# 01_-_CML3_CONNECTOR.net
KiCad netlist of a schematic drawn in Altium Designer
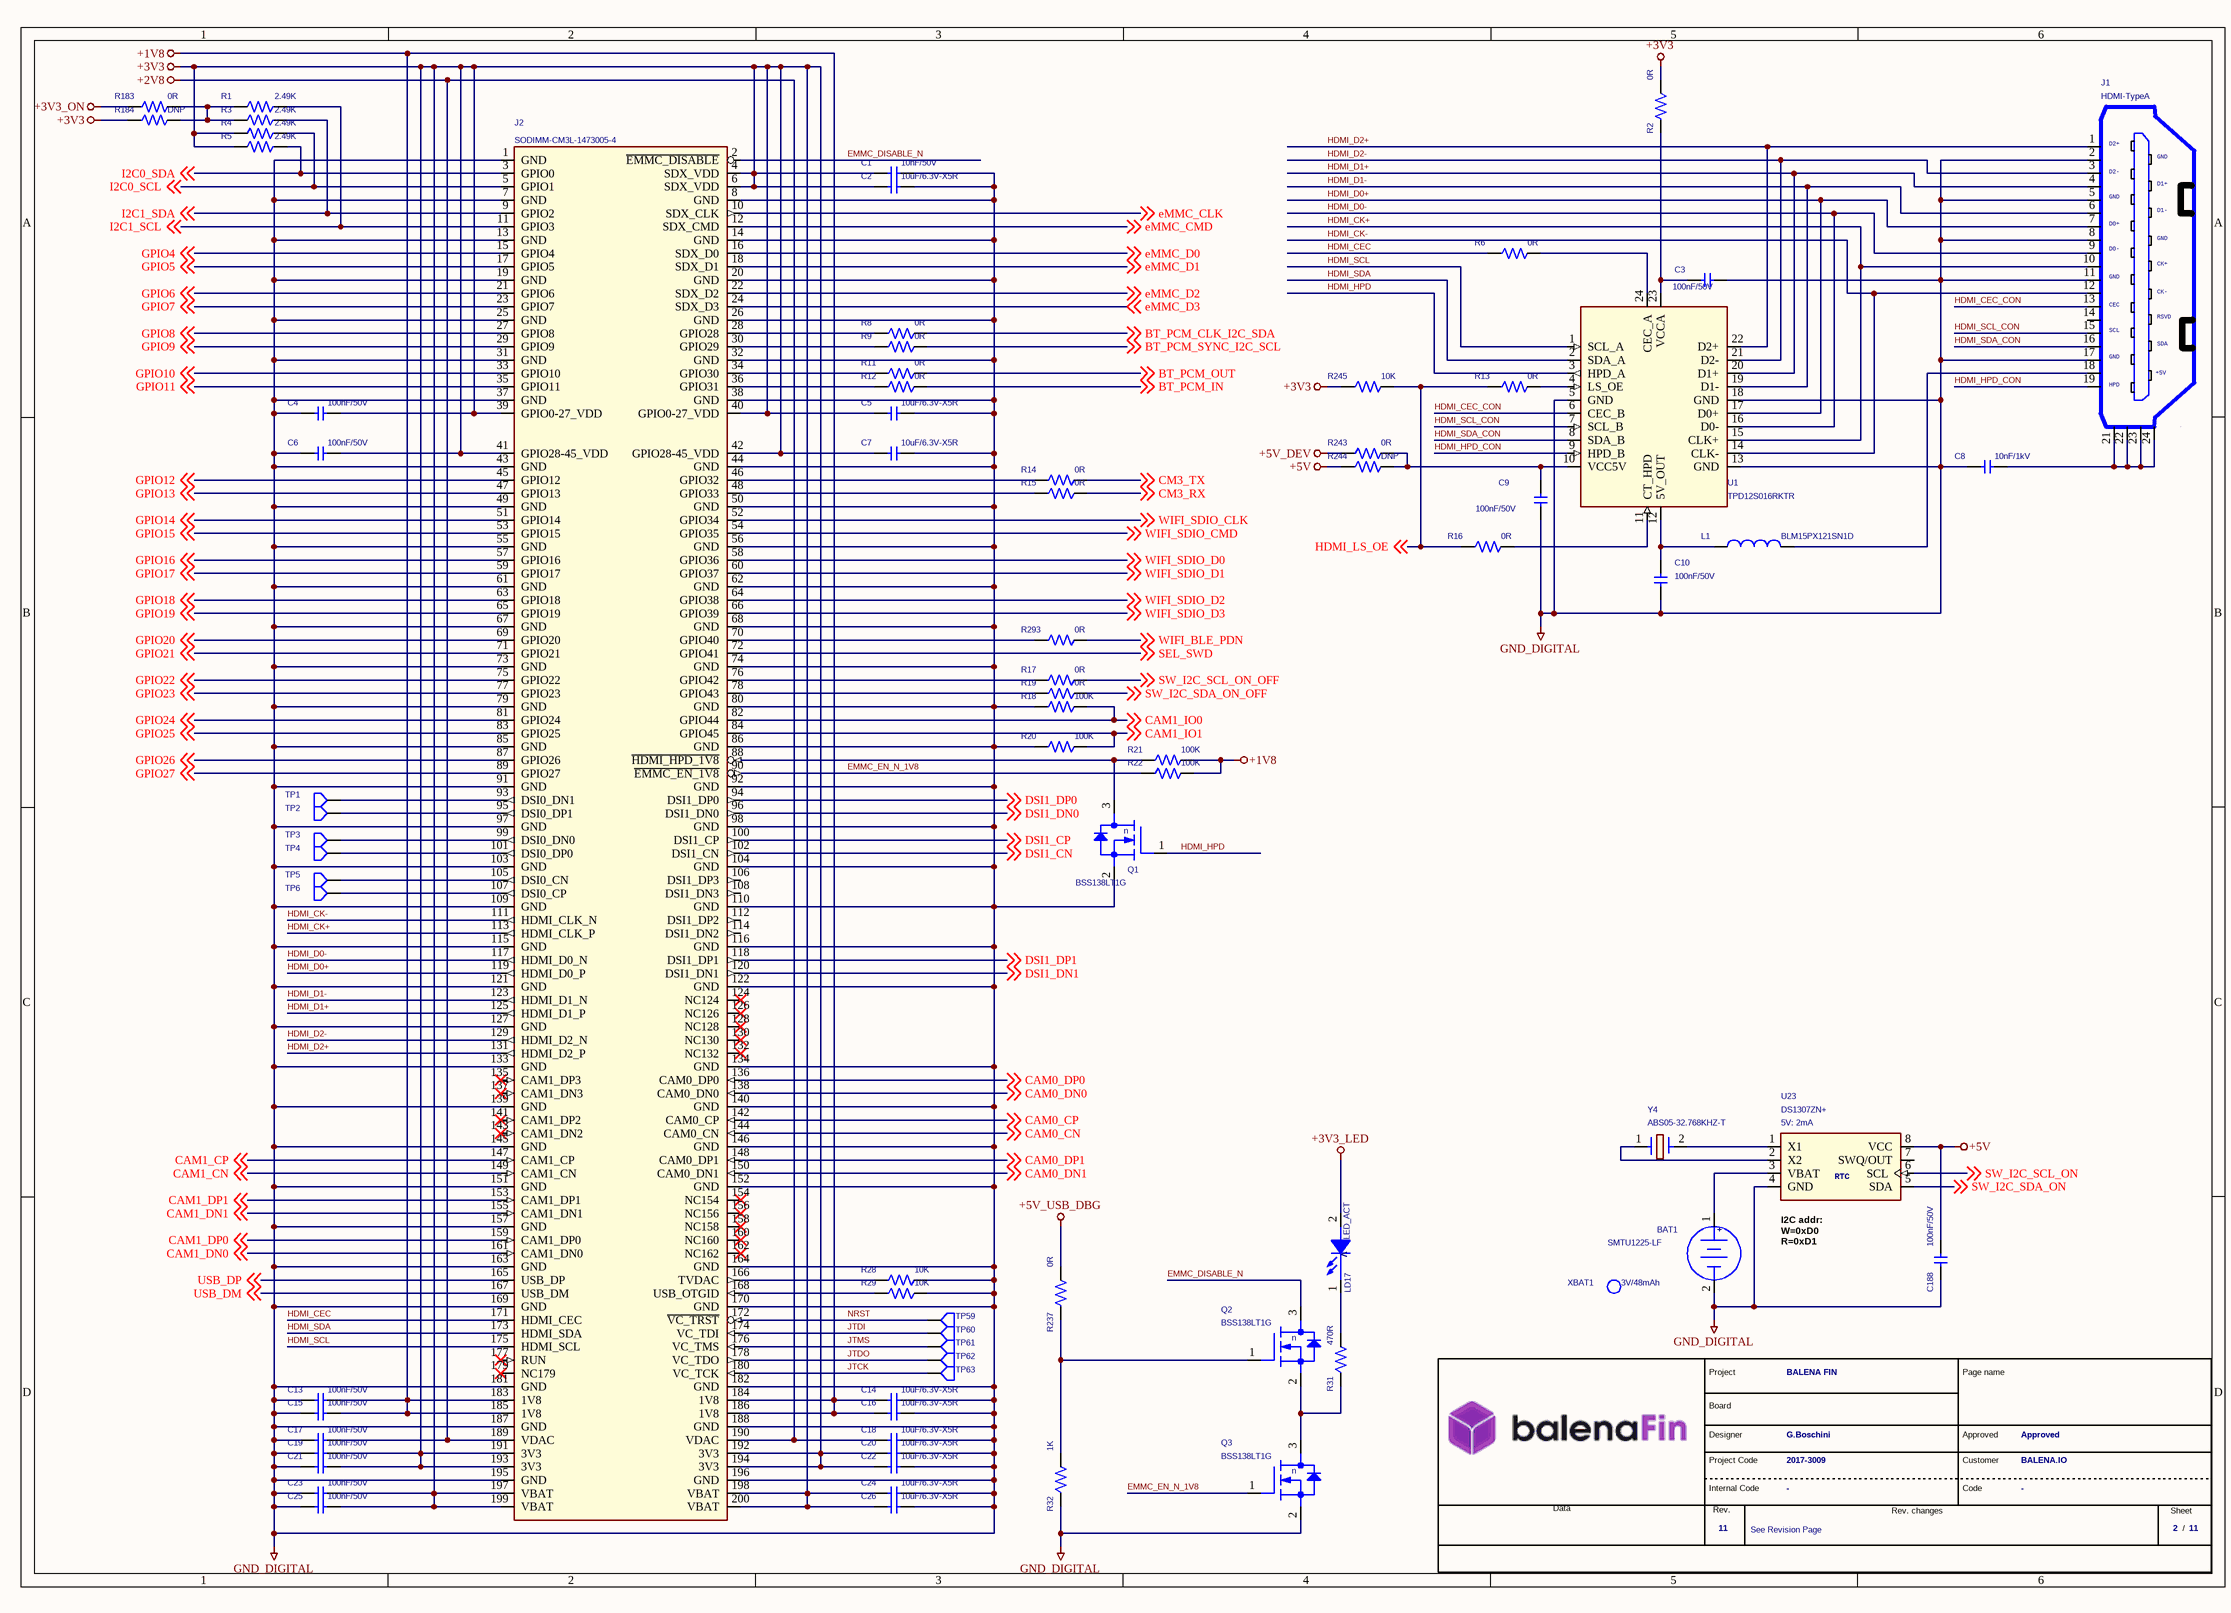
[diagram p0: 01 - CML3 CONNECTOR.SchDoc]

(export (version "E")
  (design (tool "Eeschema 10.0.6"))
  (components
    (comp (ref "BAT1")
      (value "SMTU1225-LF")
      (footprint "BAT-SMTU1225")
      (description "Coin Cell Battery Holders SFC - MNT FOR CR1225")
      (libsource (lib "*") (part "PORTA BATTERIA - SMTU1225-LF"))
    )
    (comp (ref "C1")
      (value "10nF/50V")
      (footprint "CS-C-0402")
      (description "CHIP CAP.CER. 10nF 50V 10% X7R 0402")
      (fields (field (name "MPN") "Generic"))
      (libsource (lib "*") (part "CS-C-0402-10n/50V"))
    )
    (comp (ref "C2")
      (value "10uF/6.3V-X5R")
      (footprint "CS-C-0402")
      (description "CHIP CAP.CER. 10uF 6.3V 20% X5R 0402")
      (fields (field (name "MPN") "Generic"))
      (libsource (lib "*") (part "CS-C-0402-10u/6V3-X5R"))
    )
    (comp (ref "C3")
      (value "100nF/50V")
      (footprint "CS-C-0402")
      (description "CHIP CAP.CER. 100nF 16V 10% X7R 0402")
      (fields (field (name "MPN") "Generic"))
      (libsource (lib "*") (part "CS-C-0402-100n/16V"))
    )
    (comp (ref "C4")
      (value "100nF/50V")
      (footprint "CS-C-0402")
      (description "CHIP CAP.CER. 100nF 16V 10% X7R 0402")
      (fields (field (name "MPN") "Generic"))
      (libsource (lib "*") (part "CS-C-0402-100n/16V"))
    )
    (comp (ref "C5")
      (value "10uF/6.3V-X5R")
      (footprint "CS-C-0402")
      (description "CHIP CAP.CER. 10uF 6.3V 20% X5R 0402")
      (fields (field (name "MPN") "Generic"))
      (libsource (lib "*") (part "CS-C-0402-10u/6V3-X5R"))
    )
    (comp (ref "C6")
      (value "100nF/50V")
      (footprint "CS-C-0402")
      (description "CHIP CAP.CER. 100nF 16V 10% X7R 0402")
      (fields (field (name "MPN") "Generic"))
      (libsource (lib "*") (part "CS-C-0402-100n/16V"))
    )
    (comp (ref "C7")
      (value "10uF/6.3V-X5R")
      (footprint "CS-C-0402")
      (description "CHIP CAP.CER. 10uF 6.3V 20% X5R 0402")
      (fields (field (name "MPN") "Generic"))
      (libsource (lib "*") (part "CS-C-0402-10u/6V3-X5R"))
    )
    (comp (ref "C8")
      (value "10nF/1kV")
      (footprint "CS-C-1206")
      (description "CHIP CAP.CER. 10nF 1000V 10% X7R 1206")
      (fields (field (name "MPN") "Generic"))
      (libsource (lib "*") (part "CS-C-1206-10n/1kV"))
    )
    (comp (ref "C9")
      (value "100nF/50V")
      (footprint "CS-C-0402")
      (description "CHIP CAP.CER. 100nF 16V 10% X7R 0402")
      (fields (field (name "MPN") "Generic"))
      (libsource (lib "*") (part "CS-C-0402-100n/16V"))
    )
    (comp (ref "C10")
      (value "100nF/50V")
      (footprint "CS-C-0402")
      (description "CHIP CAP.CER. 100nF 16V 10% X7R 0402")
      (fields (field (name "MPN") "Generic"))
      (libsource (lib "*") (part "CS-C-0402-100n/16V"))
    )
    (comp (ref "C13")
      (value "100nF/50V")
      (footprint "CS-C-0402")
      (description "CHIP CAP.CER. 100nF 16V 10% X7R 0402")
      (fields (field (name "MPN") "Generic"))
      (libsource (lib "*") (part "CS-C-0402-100n/16V"))
    )
    (comp (ref "C14")
      (value "10uF/6.3V-X5R")
      (footprint "CS-C-0402")
      (description "CHIP CAP.CER. 10uF 6.3V 20% X5R 0402")
      (fields (field (name "MPN") "Generic"))
      (libsource (lib "*") (part "CS-C-0402-10u/6V3-X5R"))
    )
    (comp (ref "C15")
      (value "100nF/50V")
      (footprint "CS-C-0402")
      (description "CHIP CAP.CER. 100nF 16V 10% X7R 0402")
      (fields (field (name "MPN") "Generic"))
      (libsource (lib "*") (part "CS-C-0402-100n/16V"))
    )
    (comp (ref "C16")
      (value "10uF/6.3V-X5R")
      (footprint "CS-C-0402")
      (description "CHIP CAP.CER. 10uF 6.3V 20% X5R 0402")
      (fields (field (name "MPN") "Generic"))
      (libsource (lib "*") (part "CS-C-0402-10u/6V3-X5R"))
    )
    (comp (ref "C17")
      (value "100nF/50V")
      (footprint "CS-C-0402")
      (description "CHIP CAP.CER. 100nF 16V 10% X7R 0402")
      (fields (field (name "MPN") "Generic"))
      (libsource (lib "*") (part "CS-C-0402-100n/16V"))
    )
    (comp (ref "C18")
      (value "10uF/6.3V-X5R")
      (footprint "CS-C-0402")
      (description "CHIP CAP.CER. 10uF 6.3V 20% X5R 0402")
      (fields (field (name "MPN") "Generic"))
      (libsource (lib "*") (part "CS-C-0402-10u/6V3-X5R"))
    )
    (comp (ref "C19")
      (value "100nF/50V")
      (footprint "CS-C-0402")
      (description "CHIP CAP.CER. 100nF 16V 10% X7R 0402")
      (fields (field (name "MPN") "Generic"))
      (libsource (lib "*") (part "CS-C-0402-100n/16V"))
    )
    (comp (ref "C20")
      (value "10uF/6.3V-X5R")
      (footprint "CS-C-0402")
      (description "CHIP CAP.CER. 10uF 6.3V 20% X5R 0402")
      (fields (field (name "MPN") "Generic"))
      (libsource (lib "*") (part "CS-C-0402-10u/6V3-X5R"))
    )
    (comp (ref "C21")
      (value "100nF/50V")
      (footprint "CS-C-0402")
      (description "CHIP CAP.CER. 100nF 16V 10% X7R 0402")
      (fields (field (name "MPN") "Generic"))
      (libsource (lib "*") (part "CS-C-0402-100n/16V"))
    )
    (comp (ref "C22")
      (value "10uF/6.3V-X5R")
      (footprint "CS-C-0402")
      (description "CHIP CAP.CER. 10uF 6.3V 20% X5R 0402")
      (fields (field (name "MPN") "Generic"))
      (libsource (lib "*") (part "CS-C-0402-10u/6V3-X5R"))
    )
    (comp (ref "C23")
      (value "100nF/50V")
      (footprint "CS-C-0402")
      (description "CHIP CAP.CER. 100nF 16V 10% X7R 0402")
      (fields (field (name "MPN") "Generic"))
      (libsource (lib "*") (part "CS-C-0402-100n/16V"))
    )
    (comp (ref "C24")
      (value "10uF/6.3V-X5R")
      (footprint "CS-C-0402")
      (description "CHIP CAP.CER. 10uF 6.3V 20% X5R 0402")
      (fields (field (name "MPN") "Generic"))
      (libsource (lib "*") (part "CS-C-0402-10u/6V3-X5R"))
    )
    (comp (ref "C25")
      (value "100nF/50V")
      (footprint "CS-C-0402")
      (description "CHIP CAP.CER. 100nF 16V 10% X7R 0402")
      (fields (field (name "MPN") "Generic"))
      (libsource (lib "*") (part "CS-C-0402-100n/16V"))
    )
    (comp (ref "C26")
      (value "10uF/6.3V-X5R")
      (footprint "CS-C-0402")
      (description "CHIP CAP.CER. 10uF 6.3V 20% X5R 0402")
      (fields (field (name "MPN") "Generic"))
      (libsource (lib "*") (part "CS-C-0402-10u/6V3-X5R"))
    )
    (comp (ref "C188")
      (value "100nF/50V")
      (footprint "CS-C-0402")
      (description "CHIP CAP.CER. 100nF 16V 10% X7R 0402")
      (fields (field (name "MPN") "Generic"))
      (libsource (lib "*") (part "CS-C-0402-100n/16V"))
    )
    (comp (ref "J1")
      (value "HDMI-TypeA")
      (footprint "J-19-0050-FOS-HDMI-A-CNCTECH")
      (description "HDMI Receptacle Connector - 19 Position Surface Mount, Right Angle")
      (fields (field (name "MPN") "2000-1-2-41-00-BK"))
      (libsource (lib "*") (part "HDMI - J-19-0050-FOS-HDMI-A-CNC"))
    )
    (comp (ref "J2")
      (value "SODIMM-CM3L-1473005-4")
      (footprint "J-200-0060-MOS-1473005-4")
      (description "200 Position SODIMM DDR2 - SDRAM Socket Surface Mount, Right Angle")
      (fields (field (name "MPN") "1473005-4"))
      (libsource (lib "*") (part "SODIMM - CM3L - 1473005-4"))
    )
    (comp (ref "L1")
      (value "BLM15PX121SN1D")
      (footprint "LS-0402")
      (description "FERRITE 120R 2A 25% 0402 BLM15PX121SN1D MURATA SMT")
      (libsource (lib "*") (part "FIL-BLM15PX121SN1D- 120R/2A"))
    )
    (comp (ref "LD17")
      (value "LED_ACT")
      (footprint "LD-0603")
      (description "LED Green 0603 SMT")
      (fields (field (name "MPN") "Generic"))
      (libsource (lib "*") (part "LED V - GENERICO - 0603"))
    )
    (comp (ref "Q1")
      (value "BSS138LT1G")
      (footprint "SOT23")
      (description "MOSFET N-CH 50V 220MA SOT23-3")
      (libsource (lib "*") (part "NMOS - BSS138 - 0.2A/50V"))
    )
    (comp (ref "Q2")
      (value "BSS138LT1G")
      (footprint "SOT23")
      (description "MOSFET N-CH 50V 220MA SOT23-3")
      (libsource (lib "*") (part "NMOS - BSS138 - 0.2A/50V"))
    )
    (comp (ref "Q3")
      (value "BSS138LT1G")
      (footprint "SOT23")
      (description "MOSFET N-CH 50V 220MA SOT23-3")
      (libsource (lib "*") (part "NMOS - BSS138 - 0.2A/50V"))
    )
    (comp (ref "R1")
      (value "2.49K")
      (footprint "RS-0402")
      (description "CHIP RES. 2K49 0402 1/16W 1% 100PPM/°C")
      (fields (field (name "MPN") "Generic"))
      (libsource (lib "*") (part "RS-0402-2.49k"))
    )
    (comp (ref "R2")
      (value "0R")
      (footprint "RS-0402")
      (description "CHIP RES. 0R 0402 1/16W 1%")
      (fields (field (name "MPN") "Generic"))
      (libsource (lib "*") (part "RS-0402-0r"))
    )
    (comp (ref "R3")
      (value "2.49K")
      (footprint "RS-0402")
      (description "CHIP RES. 2K49 0402 1/16W 1% 100PPM/°C")
      (fields (field (name "MPN") "Generic"))
      (libsource (lib "*") (part "RS-0402-2.49k"))
    )
    (comp (ref "R4")
      (value "2.49K")
      (footprint "RS-0402")
      (description "CHIP RES. 2K49 0402 1/16W 1% 100PPM/°C")
      (fields (field (name "MPN") "Generic"))
      (libsource (lib "*") (part "RS-0402-2.49k"))
    )
    (comp (ref "R5")
      (value "2.49K")
      (footprint "RS-0402")
      (description "CHIP RES. 2K49 0402 1/16W 1% 100PPM/°C")
      (fields (field (name "MPN") "Generic"))
      (libsource (lib "*") (part "RS-0402-2.49k"))
    )
    (comp (ref "R6")
      (value "0R")
      (footprint "RS-0402")
      (description "CHIP RES. 0R 0402 1/16W 1%")
      (fields (field (name "MPN") "Generic"))
      (libsource (lib "*") (part "RS-0402-0r"))
    )
    (comp (ref "R8")
      (value "0R")
      (footprint "RS-0402")
      (description "CHIP RES. 0R 0402 1/16W 1%")
      (fields (field (name "MPN") "Generic"))
      (libsource (lib "*") (part "RS-0402-0r"))
    )
    (comp (ref "R9")
      (value "0R")
      (footprint "RS-0402")
      (description "CHIP RES. 0R 0402 1/16W 1%")
      (fields (field (name "MPN") "Generic"))
      (libsource (lib "*") (part "RS-0402-0r"))
    )
    (comp (ref "R11")
      (value "0R")
      (footprint "RS-0402")
      (description "CHIP RES. 0R 0402 1/16W 1%")
      (fields (field (name "MPN") "Generic"))
      (libsource (lib "*") (part "RS-0402-0r"))
    )
    (comp (ref "R12")
      (value "0R")
      (footprint "RS-0402")
      (description "CHIP RES. 0R 0402 1/16W 1%")
      (fields (field (name "MPN") "Generic"))
      (libsource (lib "*") (part "RS-0402-0r"))
    )
    (comp (ref "R13")
      (value "0R")
      (footprint "RS-0402")
      (description "CHIP RES. 0R 0402 1/16W 1%")
      (fields (field (name "MPN") "Generic"))
      (libsource (lib "*") (part "RS-0402-0r"))
    )
    (comp (ref "R14")
      (value "0R")
      (footprint "RS-0402")
      (description "CHIP RES. 0R 0402 1/16W 1%")
      (fields (field (name "MPN") "Generic"))
      (libsource (lib "*") (part "RS-0402-0r"))
    )
    (comp (ref "R15")
      (value "0R")
      (footprint "RS-0402")
      (description "CHIP RES. 0R 0402 1/16W 1%")
      (fields (field (name "MPN") "Generic"))
      (libsource (lib "*") (part "RS-0402-0r"))
    )
    (comp (ref "R16")
      (value "0R")
      (footprint "RS-0402")
      (description "CHIP RES. 0R 0402 1/16W 1%")
      (fields (field (name "MPN") "Generic"))
      (libsource (lib "*") (part "RS-0402-0r"))
    )
    (comp (ref "R17")
      (value "0R")
      (footprint "RS-0402")
      (description "CHIP RES. 0R 0402 1/16W 1%")
      (fields (field (name "MPN") "Generic"))
      (libsource (lib "*") (part "RS-0402-0r"))
    )
    (comp (ref "R18")
      (value "100K")
      (footprint "RS-0402")
      (description "CHIP RES. 100K 0402 1/16W 1%")
      (fields (field (name "MPN") "Generic"))
      (libsource (lib "*") (part "RS-0402-100k"))
    )
    (comp (ref "R19")
      (value "0R")
      (footprint "RS-0402")
      (description "CHIP RES. 0R 0402 1/16W 1%")
      (fields (field (name "MPN") "Generic"))
      (libsource (lib "*") (part "RS-0402-0r"))
    )
    (comp (ref "R20")
      (value "100K")
      (footprint "RS-0402")
      (description "CHIP RES. 100K 0402 1/16W 1%")
      (fields (field (name "MPN") "Generic"))
      (libsource (lib "*") (part "RS-0402-100k"))
    )
    (comp (ref "R21")
      (value "100K")
      (footprint "RS-0402")
      (description "CHIP RES. 100K 0402 1/16W 1%")
      (fields (field (name "MPN") "Generic"))
      (libsource (lib "*") (part "RS-0402-100k"))
    )
    (comp (ref "R22")
      (value "100K")
      (footprint "RS-0402")
      (description "CHIP RES. 100K 0402 1/16W 1%")
      (fields (field (name "MPN") "Generic"))
      (libsource (lib "*") (part "RS-0402-100k"))
    )
    (comp (ref "R28")
      (value "10K")
      (footprint "RS-0402")
      (description "CHIP RES. 10K 0402 1/16W 1%")
      (fields (field (name "MPN") "Generic"))
      (libsource (lib "*") (part "RS-0402-10k"))
    )
    (comp (ref "R29")
      (value "10K")
      (footprint "RS-0402")
      (description "CHIP RES. 10K 0402 1/16W 1%")
      (fields (field (name "MPN") "Generic"))
      (libsource (lib "*") (part "RS-0402-10k"))
    )
    (comp (ref "R31")
      (value "470R")
      (footprint "RS-0402")
      (description "CHIP RES. 470R 0402 1/16W 1%")
      (fields (field (name "MPN") "Generic"))
      (libsource (lib "*") (part "RS-0402-470r"))
    )
    (comp (ref "R32")
      (value "1K")
      (footprint "RS-0402")
      (description "CHIP RES. 1K 0402 1/16W 1%")
      (fields (field (name "MPN") "Generic"))
      (libsource (lib "*") (part "RS-0402-1k"))
    )
    (comp (ref "R183")
      (value "0R")
      (footprint "RS-0402")
      (description "CHIP RES. 0R 0402 1/16W 1%")
      (fields (field (name "MPN") "Generic"))
      (libsource (lib "*") (part "RS-0402-0r"))
    )
    (comp (ref "R184")
      (value "DNP")
      (footprint "RS-0402")
      (description "CHIP RES. 0R 0402 1/10W 1%")
      (fields (field (name "MPN") "Generic"))
      (libsource (lib "*") (part "RS-0402"))
    )
    (comp (ref "R237")
      (value "0R")
      (footprint "RS-0402")
      (description "CHIP RES. 0R 0402 1/16W 1%")
      (fields (field (name "MPN") "Generic"))
      (libsource (lib "*") (part "RS-0402-0r"))
    )
    (comp (ref "R243")
      (value "0R")
      (footprint "RS-0402")
      (description "CHIP RES. 0R 0402 1/16W 1%")
      (fields (field (name "MPN") "Generic"))
      (libsource (lib "*") (part "RS-0402-0r"))
    )
    (comp (ref "R244")
      (value "DNP")
      (footprint "RS-0402")
      (description "CHIP RES. 0402")
      (fields (field (name "MPN") "Generic"))
      (libsource (lib "*") (part "RS-0402"))
    )
    (comp (ref "R245")
      (value "10K")
      (footprint "RS-0402")
      (description "CHIP RES. 10K 0402 1/16W 1%")
      (fields (field (name "MPN") "Generic"))
      (libsource (lib "*") (part "RS-0402-10k"))
    )
    (comp (ref "R293")
      (value "0R")
      (footprint "RS-0402")
      (description "CHIP RES. 0R 0402 1/16W 1%")
      (fields (field (name "MPN") "Generic"))
      (libsource (lib "*") (part "RS-0402-0r"))
    )
    (comp (ref "TP1")
      (value "TPS")
      (footprint "TPS-0100")
      (description "TEST POINT SMD")
      (fields (field (name "MPN") "TP-No-BoM"))
      (libsource (lib "*") (part "TEST POINT SMD 1 MM"))
    )
    (comp (ref "TP2")
      (value "TPS")
      (footprint "TPS-0100")
      (description "TEST POINT SMD")
      (fields (field (name "MPN") "TP-No-BoM"))
      (libsource (lib "*") (part "TEST POINT SMD 1 MM"))
    )
    (comp (ref "TP3")
      (value "TPS")
      (footprint "TPS-0100")
      (description "TEST POINT SMD")
      (fields (field (name "MPN") "TP-No-BoM"))
      (libsource (lib "*") (part "TEST POINT SMD 1 MM"))
    )
    (comp (ref "TP4")
      (value "TPS")
      (footprint "TPS-0100")
      (description "TEST POINT SMD")
      (fields (field (name "MPN") "TP-No-BoM"))
      (libsource (lib "*") (part "TEST POINT SMD 1 MM"))
    )
    (comp (ref "TP5")
      (value "TPS")
      (footprint "TPS-0100")
      (description "TEST POINT SMD")
      (fields (field (name "MPN") "TP-No-BoM"))
      (libsource (lib "*") (part "TEST POINT SMD 1 MM"))
    )
    (comp (ref "TP6")
      (value "TPS")
      (footprint "TPS-0100")
      (description "TEST POINT SMD")
      (fields (field (name "MPN") "TP-No-BoM"))
      (libsource (lib "*") (part "TEST POINT SMD 1 MM"))
    )
    (comp (ref "TP59")
      (value "TPS")
      (footprint "TPS-0100")
      (description "TEST POINT SMD")
      (fields (field (name "MPN") "TP-No-BoM"))
      (libsource (lib "*") (part "TEST POINT SMD 1 MM"))
    )
    (comp (ref "TP60")
      (value "TPS")
      (footprint "TPS-0100")
      (description "TEST POINT SMD")
      (fields (field (name "MPN") "TP-No-BoM"))
      (libsource (lib "*") (part "TEST POINT SMD 1 MM"))
    )
    (comp (ref "TP61")
      (value "TPS")
      (footprint "TPS-0100")
      (description "TEST POINT SMD")
      (fields (field (name "MPN") "TP-No-BoM"))
      (libsource (lib "*") (part "TEST POINT SMD 1 MM"))
    )
    (comp (ref "TP62")
      (value "TPS")
      (footprint "TPS-0100")
      (description "TEST POINT SMD")
      (fields (field (name "MPN") "TP-No-BoM"))
      (libsource (lib "*") (part "TEST POINT SMD 1 MM"))
    )
    (comp (ref "TP63")
      (value "TPS")
      (footprint "TPS-0100")
      (description "TEST POINT SMD")
      (fields (field (name "MPN") "TP-No-BoM"))
      (libsource (lib "*") (part "TEST POINT SMD 1 MM"))
    )
    (comp (ref "U1")
      (value "TPD12S016RKTR")
      (footprint "UFQFN24-4X2")
      (description "HDMI, I²C Buffer, ESD Protection Interface 24-UQFN (4x2)")
      (libsource (lib "*") (part "HDMI-TPD12S016RKTR-ESD PROTECT"))
    )
    (comp (ref "U23")
      (value "DS1307ZN+")
      (footprint "SOIC8")
      (description "IC RTC CLK/CALENDAR I2C 8-SOIC")
      (fields (field (name "POWER REQUIREMENTS") "5V: 2mA"))
      (libsource (lib "*") (part "RTC - DS1307ZN+"))
    )
    (comp (ref "XBAT1")
      (value "3V/48mAh")
      (description "LITHUM BATTERY 3V 48mAh (-30 / +70°C) CR1225")
      (fields (field (name "MPN") "CR1225FV-LF"))
      (libsource (lib "*") (part "LITIO - CR1225 - 48mAh/3V"))
    )
    (comp (ref "Y4")
      (value "ABS05-32.768KHZ-T")
      (footprint "Y-ABS05")
      (description "32.768kHz ±20ppm Crystal 12.5pF 90 kOhms 2-SMD, No  Lead D=1.6x1")
      (libsource (lib "*") (part "QUARZO-ABS05-32.768KHZ-T"))
    )
  )
  (nets
    (net (code "1") (name "+1V8") (class "Default")
      (node (ref "C13") (pin "2") (pinfunction "2_2") (pintype "passive"))
      (node (ref "C14") (pin "1") (pinfunction "1_1") (pintype "passive"))
      (node (ref "C15") (pin "2") (pinfunction "2_2") (pintype "passive"))
      (node (ref "C16") (pin "1") (pinfunction "1_1") (pintype "passive"))
      (node (ref "J2") (pin "183") (pinfunction "1V8_183") (pintype "power_in"))
      (node (ref "J2") (pin "184") (pinfunction "1V8_184") (pintype "power_in"))
      (node (ref "J2") (pin "185") (pinfunction "1V8_185") (pintype "power_in"))
      (node (ref "J2") (pin "186") (pinfunction "1V8_186") (pintype "power_in"))
      (node (ref "R21") (pin "2") (pinfunction "2_2") (pintype "passive"))
      (node (ref "R22") (pin "2") (pinfunction "2_2") (pintype "passive"))
    )
    (net (code "2") (name "+2V8") (class "Default")
      (node (ref "C17") (pin "2") (pinfunction "2_2") (pintype "passive"))
      (node (ref "C18") (pin "1") (pinfunction "1_1") (pintype "passive"))
      (node (ref "J2") (pin "189") (pinfunction "VDAC_189") (pintype "power_in"))
      (node (ref "J2") (pin "190") (pinfunction "VDAC_190") (pintype "power_in"))
    )
    (net (code "3") (name "+3V3") (class "Default")
      (node (ref "C1") (pin "1") (pinfunction "1_1") (pintype "passive"))
      (node (ref "C19") (pin "2") (pinfunction "2_2") (pintype "passive"))
      (node (ref "C2") (pin "1") (pinfunction "1_1") (pintype "passive"))
      (node (ref "C20") (pin "1") (pinfunction "1_1") (pintype "passive"))
      (node (ref "C21") (pin "2") (pinfunction "2_2") (pintype "passive"))
      (node (ref "C22") (pin "1") (pinfunction "1_1") (pintype "passive"))
      (node (ref "C23") (pin "2") (pinfunction "2_2") (pintype "passive"))
      (node (ref "C24") (pin "1") (pinfunction "1_1") (pintype "passive"))
      (node (ref "C25") (pin "2") (pinfunction "2_2") (pintype "passive"))
      (node (ref "C26") (pin "1") (pinfunction "1_1") (pintype "passive"))
      (node (ref "C4") (pin "2") (pinfunction "2_2") (pintype "passive"))
      (node (ref "C5") (pin "1") (pinfunction "1_1") (pintype "passive"))
      (node (ref "C6") (pin "2") (pinfunction "2_2") (pintype "passive"))
      (node (ref "C7") (pin "1") (pinfunction "1_1") (pintype "passive"))
      (node (ref "J2") (pin "191") (pinfunction "3V3_191") (pintype "power_in"))
      (node (ref "J2") (pin "192") (pinfunction "3V3_192") (pintype "power_in"))
      (node (ref "J2") (pin "193") (pinfunction "3V3_193") (pintype "power_in"))
      (node (ref "J2") (pin "194") (pinfunction "3V3_194") (pintype "power_in"))
      (node (ref "J2") (pin "197") (pinfunction "VBAT_197") (pintype "power_in"))
      (node (ref "J2") (pin "198") (pinfunction "VBAT_198") (pintype "power_in"))
      (node (ref "J2") (pin "199") (pinfunction "VBAT_199") (pintype "power_in"))
      (node (ref "J2") (pin "200") (pinfunction "VBAT_200") (pintype "power_in"))
      (node (ref "J2") (pin "39") (pinfunction "GPIO0-27_VDD_39") (pintype "power_in"))
      (node (ref "J2") (pin "4") (pinfunction "SDX_VDD_4") (pintype "power_in"))
      (node (ref "J2") (pin "40") (pinfunction "GPIO0-27_VDD_40") (pintype "power_in"))
      (node (ref "J2") (pin "41") (pinfunction "GPIO28-45_VDD_41") (pintype "power_in"))
      (node (ref "J2") (pin "42") (pinfunction "GPIO28-45_VDD_42") (pintype "power_in"))
      (node (ref "J2") (pin "6") (pinfunction "SDX_VDD_6") (pintype "power_in"))
      (node (ref "R184") (pin "1") (pinfunction "1_1") (pintype "passive"))
      (node (ref "R2") (pin "2") (pinfunction "2_2") (pintype "passive"))
      (node (ref "R245") (pin "1") (pinfunction "1_1") (pintype "passive"))
      (node (ref "R4") (pin "2") (pinfunction "2_2") (pintype "passive"))
      (node (ref "R5") (pin "2") (pinfunction "2_2") (pintype "passive"))
    )
    (net (code "4") (name "+3V3_LED") (class "Default")
      (node (ref "LD17") (pin "2") (pinfunction "A_2") (pintype "passive"))
    )
    (net (code "5") (name "+3V3_ON") (class "Default")
      (node (ref "R183") (pin "1") (pinfunction "1_1") (pintype "passive"))
    )
    (net (code "6") (name "+5V") (class "Default")
      (node (ref "C188") (pin "1") (pinfunction "1_1") (pintype "passive"))
      (node (ref "R244") (pin "1") (pinfunction "1_1") (pintype "passive"))
      (node (ref "U23") (pin "8") (pinfunction "VCC_8") (pintype "power_in"))
    )
    (net (code "7") (name "+5V_DEV") (class "Default")
      (node (ref "R243") (pin "1") (pinfunction "1_1") (pintype "passive"))
    )
    (net (code "8") (name "+5V_USB_DBG") (class "Default")
      (node (ref "R237") (pin "2") (pinfunction "2_2") (pintype "passive"))
    )
    (net (code "9") (name "/EMMC_DISABLE_N") (class "Default")
      (node (ref "J2") (pin "2") (pinfunction "~{EMMC_DISABLE}_2") (pintype "passive"))
      (node (ref "Q2") (pin "3") (pinfunction "D_3") (pintype "passive"))
    )
    (net (code "10") (name "/EMMC_EN_N_1V8") (class "Default")
      (node (ref "J2") (pin "90") (pinfunction "~{EMMC_EN_1V8}_90") (pintype "output"))
      (node (ref "Q3") (pin "1") (pinfunction "G_1") (pintype "passive"))
      (node (ref "R22") (pin "1") (pinfunction "1_1") (pintype "passive"))
    )
    (net (code "11") (name "/HDMI_CEC") (class "Default")
      (node (ref "J2") (pin "171") (pinfunction "HDMI_CEC_171") (pintype "bidirectional"))
      (node (ref "R6") (pin "1") (pinfunction "1_1") (pintype "passive"))
    )
    (net (code "12") (name "/HDMI_CEC_CON") (class "Default")
      (node (ref "J1") (pin "13") (pinfunction "CEC_13") (pintype "passive"))
      (node (ref "U1") (pin "6") (pinfunction "CEC_B_6") (pintype "bidirectional"))
    )
    (net (code "13") (name "/HDMI_CK+") (class "Default")
      (node (ref "J1") (pin "10") (pinfunction "CK+_10") (pintype "passive"))
      (node (ref "J2") (pin "113") (pinfunction "HDMI_CLK_P_113") (pintype "output"))
      (node (ref "U1") (pin "15") (pinfunction "CLK+_15") (pintype "passive"))
    )
    (net (code "14") (name "/HDMI_CK-") (class "Default")
      (node (ref "J1") (pin "12") (pinfunction "CK-_12") (pintype "passive"))
      (node (ref "J2") (pin "111") (pinfunction "HDMI_CLK_N_111") (pintype "output"))
      (node (ref "U1") (pin "14") (pinfunction "CLK-_14") (pintype "passive"))
    )
    (net (code "15") (name "/HDMI_D0+") (class "Default")
      (node (ref "J1") (pin "7") (pinfunction "D0+_7") (pintype "passive"))
      (node (ref "J2") (pin "119") (pinfunction "HDMI_D0_P_119") (pintype "output"))
      (node (ref "U1") (pin "17") (pinfunction "D0+_17") (pintype "passive"))
    )
    (net (code "16") (name "/HDMI_D0-") (class "Default")
      (node (ref "J1") (pin "9") (pinfunction "D0-_9") (pintype "passive"))
      (node (ref "J2") (pin "117") (pinfunction "HDMI_D0_N_117") (pintype "output"))
      (node (ref "U1") (pin "16") (pinfunction "D0-_16") (pintype "passive"))
    )
    (net (code "17") (name "/HDMI_D1+") (class "Default")
      (node (ref "J1") (pin "4") (pinfunction "D1+_4") (pintype "passive"))
      (node (ref "J2") (pin "125") (pinfunction "HDMI_D1_P_125") (pintype "output"))
      (node (ref "U1") (pin "20") (pinfunction "D1+_20") (pintype "passive"))
    )
    (net (code "18") (name "/HDMI_D1-") (class "Default")
      (node (ref "J1") (pin "6") (pinfunction "D1-_6") (pintype "passive"))
      (node (ref "J2") (pin "123") (pinfunction "HDMI_D1_N_123") (pintype "output"))
      (node (ref "U1") (pin "19") (pinfunction "D1-_19") (pintype "passive"))
    )
    (net (code "19") (name "/HDMI_D2+") (class "Default")
      (node (ref "J1") (pin "1") (pinfunction "D2+_1") (pintype "passive"))
      (node (ref "J2") (pin "131") (pinfunction "HDMI_D2_P_131") (pintype "output"))
      (node (ref "U1") (pin "22") (pinfunction "D2+_22") (pintype "passive"))
    )
    (net (code "20") (name "/HDMI_D2-") (class "Default")
      (node (ref "J1") (pin "3") (pinfunction "D2-_3") (pintype "passive"))
      (node (ref "J2") (pin "129") (pinfunction "HDMI_D2_N_129") (pintype "output"))
      (node (ref "U1") (pin "21") (pinfunction "D2-_21") (pintype "passive"))
    )
    (net (code "21") (name "/HDMI_HPD") (class "Default")
      (node (ref "Q1") (pin "1") (pinfunction "G_1") (pintype "passive"))
      (node (ref "U1") (pin "3") (pinfunction "HPD_A_3") (pintype "output"))
    )
    (net (code "22") (name "/HDMI_HPD_CON") (class "Default")
      (node (ref "J1") (pin "19") (pinfunction "HDP_19") (pintype "passive"))
      (node (ref "U1") (pin "9") (pinfunction "HPD_B_9") (pintype "input"))
    )
    (net (code "23") (name "/HDMI_SCL") (class "Default")
      (node (ref "J2") (pin "175") (pinfunction "HDMI_SCL_175") (pintype "bidirectional"))
      (node (ref "U1") (pin "1") (pinfunction "SCL_A_1") (pintype "input"))
    )
    (net (code "24") (name "/HDMI_SCL_CON") (class "Default")
      (node (ref "J1") (pin "15") (pinfunction "SCL_15") (pintype "passive"))
      (node (ref "U1") (pin "7") (pinfunction "SCL_B_7") (pintype "input"))
    )
    (net (code "25") (name "/HDMI_SDA") (class "Default")
      (node (ref "J2") (pin "173") (pinfunction "HDMI_SDA_173") (pintype "bidirectional"))
      (node (ref "U1") (pin "2") (pinfunction "SDA_A_2") (pintype "bidirectional"))
    )
    (net (code "26") (name "/HDMI_SDA_CON") (class "Default")
      (node (ref "J1") (pin "16") (pinfunction "SDA_16") (pintype "passive"))
      (node (ref "U1") (pin "8") (pinfunction "SDA_B_8") (pintype "bidirectional"))
    )
    (net (code "27") (name "/JTCK") (class "Default")
      (node (ref "J2") (pin "180") (pinfunction "VC_TCK_180") (pintype "input"))
      (node (ref "TP63") (pin "1") (pinfunction "TP_1") (pintype "passive"))
    )
    (net (code "28") (name "/JTDI") (class "Default")
      (node (ref "J2") (pin "174") (pinfunction "VC_TDI_174") (pintype "input"))
      (node (ref "TP60") (pin "1") (pinfunction "TP_1") (pintype "passive"))
    )
    (net (code "29") (name "/JTDO") (class "Default")
      (node (ref "J2") (pin "178") (pinfunction "VC_TDO_178") (pintype "output"))
      (node (ref "TP62") (pin "1") (pinfunction "TP_1") (pintype "passive"))
    )
    (net (code "30") (name "/JTMS") (class "Default")
      (node (ref "J2") (pin "176") (pinfunction "VC_TMS_176") (pintype "input"))
      (node (ref "TP61") (pin "1") (pinfunction "TP_1") (pintype "passive"))
    )
    (net (code "31") (name "/NRST") (class "Default")
      (node (ref "J2") (pin "172") (pinfunction "~{VC_TRST}_172") (pintype "input"))
      (node (ref "TP59") (pin "1") (pinfunction "TP_1") (pintype "passive"))
    )
    (net (code "32") (name "BT_PCM_CLK_I2C_SDA") (class "Default")
      (node (ref "R8") (pin "2") (pinfunction "2_2") (pintype "passive"))
    )
    (net (code "33") (name "BT_PCM_IN") (class "Default")
      (node (ref "R12") (pin "2") (pinfunction "2_2") (pintype "passive"))
    )
    (net (code "34") (name "BT_PCM_OUT") (class "Default")
      (node (ref "R11") (pin "2") (pinfunction "2_2") (pintype "passive"))
    )
    (net (code "35") (name "BT_PCM_SYNC_I2C_SCL") (class "Default")
      (node (ref "R9") (pin "2") (pinfunction "2_2") (pintype "passive"))
    )
    (net (code "36") (name "CAM0_CN") (class "Default")
      (node (ref "J2") (pin "144") (pinfunction "CAM0_CN_144") (pintype "input"))
    )
    (net (code "37") (name "CAM0_CP") (class "Default")
      (node (ref "J2") (pin "142") (pinfunction "CAM0_CP_142") (pintype "input"))
    )
    (net (code "38") (name "CAM0_DN0") (class "Default")
      (node (ref "J2") (pin "138") (pinfunction "CAM0_DN0_138") (pintype "input"))
    )
    (net (code "39") (name "CAM0_DN1") (class "Default")
      (node (ref "J2") (pin "150") (pinfunction "CAM0_DN1_150") (pintype "input"))
    )
    (net (code "40") (name "CAM0_DP0") (class "Default")
      (node (ref "J2") (pin "136") (pinfunction "CAM0_DP0_136") (pintype "input"))
    )
    (net (code "41") (name "CAM0_DP1") (class "Default")
      (node (ref "J2") (pin "148") (pinfunction "CAM0_DP1_148") (pintype "input"))
    )
    (net (code "42") (name "CAM1_CN") (class "Default")
      (node (ref "J2") (pin "149") (pinfunction "CAM1_CN_149") (pintype "input"))
    )
    (net (code "43") (name "CAM1_CP") (class "Default")
      (node (ref "J2") (pin "147") (pinfunction "CAM1_CP_147") (pintype "input"))
    )
    (net (code "44") (name "CAM1_DN0") (class "Default")
      (node (ref "J2") (pin "161") (pinfunction "CAM1_DN0_161") (pintype "input"))
    )
    (net (code "45") (name "CAM1_DN1") (class "Default")
      (node (ref "J2") (pin "155") (pinfunction "CAM1_DN1_155") (pintype "input"))
    )
    (net (code "46") (name "CAM1_DP0") (class "Default")
      (node (ref "J2") (pin "159") (pinfunction "CAM1_DP0_159") (pintype "input"))
    )
    (net (code "47") (name "CAM1_DP1") (class "Default")
      (node (ref "J2") (pin "153") (pinfunction "CAM1_DP1_153") (pintype "input"))
    )
    (net (code "48") (name "CAM1_IO0") (class "Default")
      (node (ref "J2") (pin "82") (pinfunction "GPIO44_82") (pintype "bidirectional"))
      (node (ref "R18") (pin "2") (pinfunction "2_2") (pintype "passive"))
    )
    (net (code "49") (name "CAM1_IO1") (class "Default")
      (node (ref "J2") (pin "84") (pinfunction "GPIO45_84") (pintype "bidirectional"))
      (node (ref "R20") (pin "2") (pinfunction "2_2") (pintype "passive"))
    )
    (net (code "50") (name "CM3_RX") (class "Default")
      (node (ref "R15") (pin "2") (pinfunction "2_2") (pintype "passive"))
    )
    (net (code "51") (name "CM3_TX") (class "Default")
      (node (ref "R14") (pin "2") (pinfunction "2_2") (pintype "passive"))
    )
    (net (code "52") (name "DSI1_CN") (class "Default")
      (node (ref "J2") (pin "102") (pinfunction "DSI1_CN_102") (pintype "output"))
    )
    (net (code "53") (name "DSI1_CP") (class "Default")
      (node (ref "J2") (pin "100") (pinfunction "DSI1_CP_100") (pintype "output"))
    )
    (net (code "54") (name "DSI1_DN0") (class "Default")
      (node (ref "J2") (pin "96") (pinfunction "DSI1_DN0_96") (pintype "output"))
    )
    (net (code "55") (name "DSI1_DN1") (class "Default")
      (node (ref "J2") (pin "120") (pinfunction "DSI1_DN1_120") (pintype "output"))
    )
    (net (code "56") (name "DSI1_DP0") (class "Default")
      (node (ref "J2") (pin "94") (pinfunction "DSI1_DP0_94") (pintype "output"))
    )
    (net (code "57") (name "DSI1_DP1") (class "Default")
      (node (ref "J2") (pin "118") (pinfunction "DSI1_DP1_118") (pintype "output"))
    )
    (net (code "58") (name "GND_DIGITAL") (class "Default")
      (node (ref "BAT1") (pin "2") (pinfunction "-_2") (pintype "passive"))
      (node (ref "C1") (pin "2") (pinfunction "2_2") (pintype "passive"))
      (node (ref "C10") (pin "2") (pinfunction "2_2") (pintype "passive"))
      (node (ref "C13") (pin "1") (pinfunction "1_1") (pintype "passive"))
      (node (ref "C14") (pin "2") (pinfunction "2_2") (pintype "passive"))
      (node (ref "C15") (pin "1") (pinfunction "1_1") (pintype "passive"))
      (node (ref "C16") (pin "2") (pinfunction "2_2") (pintype "passive"))
      (node (ref "C17") (pin "1") (pinfunction "1_1") (pintype "passive"))
      (node (ref "C18") (pin "2") (pinfunction "2_2") (pintype "passive"))
      (node (ref "C188") (pin "2") (pinfunction "2_2") (pintype "passive"))
      (node (ref "C19") (pin "1") (pinfunction "1_1") (pintype "passive"))
      (node (ref "C2") (pin "2") (pinfunction "2_2") (pintype "passive"))
      (node (ref "C20") (pin "2") (pinfunction "2_2") (pintype "passive"))
      (node (ref "C21") (pin "1") (pinfunction "1_1") (pintype "passive"))
      (node (ref "C22") (pin "2") (pinfunction "2_2") (pintype "passive"))
      (node (ref "C23") (pin "1") (pinfunction "1_1") (pintype "passive"))
      (node (ref "C24") (pin "2") (pinfunction "2_2") (pintype "passive"))
      (node (ref "C25") (pin "1") (pinfunction "1_1") (pintype "passive"))
      (node (ref "C26") (pin "2") (pinfunction "2_2") (pintype "passive"))
      (node (ref "C3") (pin "2") (pinfunction "2_2") (pintype "passive"))
      (node (ref "C4") (pin "1") (pinfunction "1_1") (pintype "passive"))
      (node (ref "C5") (pin "2") (pinfunction "2_2") (pintype "passive"))
      (node (ref "C6") (pin "1") (pinfunction "1_1") (pintype "passive"))
      (node (ref "C7") (pin "2") (pinfunction "2_2") (pintype "passive"))
      (node (ref "C8") (pin "1") (pinfunction "1_1") (pintype "passive"))
      (node (ref "C9") (pin "2") (pinfunction "2_2") (pintype "passive"))
      (node (ref "J1") (pin "11") (pinfunction "GND_11_11") (pintype "power_in"))
      (node (ref "J1") (pin "17") (pinfunction "GND_17_17") (pintype "power_in"))
      (node (ref "J1") (pin "2") (pinfunction "GND_2_2") (pintype "power_in"))
      (node (ref "J1") (pin "5") (pinfunction "GND_5_5") (pintype "power_in"))
      (node (ref "J1") (pin "8") (pinfunction "GND_8_8") (pintype "power_in"))
      (node (ref "J2") (pin "1") (pinfunction "GND_1") (pintype "power_in"))
      (node (ref "J2") (pin "103") (pinfunction "GND_103") (pintype "power_in"))
      (node (ref "J2") (pin "104") (pinfunction "GND_104") (pintype "power_in"))
      (node (ref "J2") (pin "109") (pinfunction "GND_109") (pintype "power_in"))
      (node (ref "J2") (pin "110") (pinfunction "GND_110") (pintype "power_in"))
      (node (ref "J2") (pin "115") (pinfunction "GND_115") (pintype "power_in"))
      (node (ref "J2") (pin "116") (pinfunction "GND_116") (pintype "power_in"))
      (node (ref "J2") (pin "121") (pinfunction "GND_121") (pintype "power_in"))
      (node (ref "J2") (pin "122") (pinfunction "GND_122") (pintype "power_in"))
      (node (ref "J2") (pin "127") (pinfunction "GND_127") (pintype "power_in"))
      (node (ref "J2") (pin "13") (pinfunction "GND_13") (pintype "power_in"))
      (node (ref "J2") (pin "133") (pinfunction "GND_133") (pintype "power_in"))
      (node (ref "J2") (pin "134") (pinfunction "GND_134") (pintype "power_in"))
      (node (ref "J2") (pin "139") (pinfunction "GND_139") (pintype "power_in"))
      (node (ref "J2") (pin "14") (pinfunction "GND_14") (pintype "power_in"))
      (node (ref "J2") (pin "140") (pinfunction "GND_140") (pintype "power_in"))
      (node (ref "J2") (pin "145") (pinfunction "GND_145") (pintype "power_in"))
      (node (ref "J2") (pin "146") (pinfunction "GND_146") (pintype "power_in"))
      (node (ref "J2") (pin "151") (pinfunction "GND_151") (pintype "power_in"))
      (node (ref "J2") (pin "152") (pinfunction "GND_152") (pintype "power_in"))
      (node (ref "J2") (pin "157") (pinfunction "GND_157") (pintype "power_in"))
      (node (ref "J2") (pin "163") (pinfunction "GND_163") (pintype "power_in"))
      (node (ref "J2") (pin "164") (pinfunction "GND_164") (pintype "power_in"))
      (node (ref "J2") (pin "169") (pinfunction "GND_169") (pintype "power_in"))
      (node (ref "J2") (pin "170") (pinfunction "GND_170") (pintype "power_in"))
      (node (ref "J2") (pin "181") (pinfunction "GND_181") (pintype "power_in"))
      (node (ref "J2") (pin "182") (pinfunction "GND_182") (pintype "power_in"))
      (node (ref "J2") (pin "187") (pinfunction "GND_187") (pintype "power_in"))
      (node (ref "J2") (pin "188") (pinfunction "GND_188") (pintype "power_in"))
      (node (ref "J2") (pin "19") (pinfunction "GND_19") (pintype "power_in"))
      (node (ref "J2") (pin "195") (pinfunction "GND_195") (pintype "power_in"))
      (node (ref "J2") (pin "196") (pinfunction "GND_196") (pintype "power_in"))
      (node (ref "J2") (pin "20") (pinfunction "GND_20") (pintype "power_in"))
      (node (ref "J2") (pin "25") (pinfunction "GND_25") (pintype "power_in"))
      (node (ref "J2") (pin "26") (pinfunction "GND_26") (pintype "power_in"))
      (node (ref "J2") (pin "31") (pinfunction "GND_31") (pintype "power_in"))
      (node (ref "J2") (pin "32") (pinfunction "GND_32") (pintype "power_in"))
      (node (ref "J2") (pin "37") (pinfunction "GND_37") (pintype "power_in"))
      (node (ref "J2") (pin "38") (pinfunction "GND_38") (pintype "power_in"))
      (node (ref "J2") (pin "43") (pinfunction "GND_43") (pintype "power_in"))
      (node (ref "J2") (pin "44") (pinfunction "GND_44") (pintype "power_in"))
      (node (ref "J2") (pin "49") (pinfunction "GND_49") (pintype "power_in"))
      (node (ref "J2") (pin "50") (pinfunction "GND_50") (pintype "power_in"))
      (node (ref "J2") (pin "55") (pinfunction "GND_55") (pintype "power_in"))
      (node (ref "J2") (pin "56") (pinfunction "GND_56") (pintype "power_in"))
      (node (ref "J2") (pin "61") (pinfunction "GND_61") (pintype "power_in"))
      (node (ref "J2") (pin "62") (pinfunction "GND_62") (pintype "power_in"))
      (node (ref "J2") (pin "67") (pinfunction "GND_67") (pintype "power_in"))
      (node (ref "J2") (pin "68") (pinfunction "GND_68") (pintype "power_in"))
      (node (ref "J2") (pin "7") (pinfunction "GND_7") (pintype "power_in"))
      (node (ref "J2") (pin "73") (pinfunction "GND_73") (pintype "power_in"))
      (node (ref "J2") (pin "74") (pinfunction "GND_74") (pintype "power_in"))
      (node (ref "J2") (pin "79") (pinfunction "GND_79") (pintype "power_in"))
      (node (ref "J2") (pin "8") (pinfunction "GND_8") (pintype "power_in"))
      (node (ref "J2") (pin "80") (pinfunction "GND_80") (pintype "power_in"))
      (node (ref "J2") (pin "85") (pinfunction "GND_85") (pintype "power_in"))
      (node (ref "J2") (pin "86") (pinfunction "GND_86") (pintype "power_in"))
      (node (ref "J2") (pin "91") (pinfunction "GND_91") (pintype "power_in"))
      (node (ref "J2") (pin "92") (pinfunction "GND_92") (pintype "power_in"))
      (node (ref "J2") (pin "97") (pinfunction "GND_97") (pintype "power_in"))
      (node (ref "J2") (pin "98") (pinfunction "GND_98") (pintype "power_in"))
      (node (ref "Q1") (pin "2") (pinfunction "S_2") (pintype "passive"))
      (node (ref "Q3") (pin "2") (pinfunction "S_2") (pintype "passive"))
      (node (ref "R18") (pin "1") (pinfunction "1_1") (pintype "passive"))
      (node (ref "R20") (pin "1") (pinfunction "1_1") (pintype "passive"))
      (node (ref "R28") (pin "2") (pinfunction "2_2") (pintype "passive"))
      (node (ref "R29") (pin "2") (pinfunction "2_2") (pintype "passive"))
      (node (ref "R32") (pin "1") (pinfunction "1_1") (pintype "passive"))
      (node (ref "U1") (pin "13") (pinfunction "GND_13") (pintype "power_in"))
      (node (ref "U1") (pin "18") (pinfunction "GND_18") (pintype "power_in"))
      (node (ref "U1") (pin "5") (pinfunction "GND_5") (pintype "power_in"))
      (node (ref "U23") (pin "4") (pinfunction "GND_4") (pintype "power_in"))
    )
    (net (code "59") (name "GPIO4") (class "Default")
      (node (ref "J2") (pin "15") (pinfunction "GPIO4_15") (pintype "bidirectional"))
    )
    (net (code "60") (name "GPIO5") (class "Default")
      (node (ref "J2") (pin "17") (pinfunction "GPIO5_17") (pintype "bidirectional"))
    )
    (net (code "61") (name "GPIO6") (class "Default")
      (node (ref "J2") (pin "21") (pinfunction "GPIO6_21") (pintype "bidirectional"))
    )
    (net (code "62") (name "GPIO7") (class "Default")
      (node (ref "J2") (pin "23") (pinfunction "GPIO7_23") (pintype "bidirectional"))
    )
    (net (code "63") (name "GPIO8") (class "Default")
      (node (ref "J2") (pin "27") (pinfunction "GPIO8_27") (pintype "bidirectional"))
    )
    (net (code "64") (name "GPIO9") (class "Default")
      (node (ref "J2") (pin "29") (pinfunction "GPIO9_29") (pintype "bidirectional"))
    )
    (net (code "65") (name "GPIO10") (class "Default")
      (node (ref "J2") (pin "33") (pinfunction "GPIO10_33") (pintype "bidirectional"))
    )
    (net (code "66") (name "GPIO11") (class "Default")
      (node (ref "J2") (pin "35") (pinfunction "GPIO11_35") (pintype "bidirectional"))
    )
    (net (code "67") (name "GPIO12") (class "Default")
      (node (ref "J2") (pin "45") (pinfunction "GPIO12_45") (pintype "bidirectional"))
    )
    (net (code "68") (name "GPIO13") (class "Default")
      (node (ref "J2") (pin "47") (pinfunction "GPIO13_47") (pintype "bidirectional"))
    )
    (net (code "69") (name "GPIO14") (class "Default")
      (node (ref "J2") (pin "51") (pinfunction "GPIO14_51") (pintype "bidirectional"))
    )
    (net (code "70") (name "GPIO15") (class "Default")
      (node (ref "J2") (pin "53") (pinfunction "GPIO15_53") (pintype "bidirectional"))
    )
    (net (code "71") (name "GPIO16") (class "Default")
      (node (ref "J2") (pin "57") (pinfunction "GPIO16_57") (pintype "bidirectional"))
    )
    (net (code "72") (name "GPIO17") (class "Default")
      (node (ref "J2") (pin "59") (pinfunction "GPIO17_59") (pintype "bidirectional"))
    )
    (net (code "73") (name "GPIO18") (class "Default")
      (node (ref "J2") (pin "63") (pinfunction "GPIO18_63") (pintype "bidirectional"))
    )
    (net (code "74") (name "GPIO19") (class "Default")
      (node (ref "J2") (pin "65") (pinfunction "GPIO19_65") (pintype "bidirectional"))
    )
    (net (code "75") (name "GPIO20") (class "Default")
      (node (ref "J2") (pin "69") (pinfunction "GPIO20_69") (pintype "bidirectional"))
    )
    (net (code "76") (name "GPIO21") (class "Default")
      (node (ref "J2") (pin "71") (pinfunction "GPIO21_71") (pintype "bidirectional"))
    )
    (net (code "77") (name "GPIO22") (class "Default")
      (node (ref "J2") (pin "75") (pinfunction "GPIO22_75") (pintype "bidirectional"))
    )
    (net (code "78") (name "GPIO23") (class "Default")
      (node (ref "J2") (pin "77") (pinfunction "GPIO23_77") (pintype "bidirectional"))
    )
    (net (code "79") (name "GPIO24") (class "Default")
      (node (ref "J2") (pin "81") (pinfunction "GPIO24_81") (pintype "bidirectional"))
    )
    (net (code "80") (name "GPIO25") (class "Default")
      (node (ref "J2") (pin "83") (pinfunction "GPIO25_83") (pintype "bidirectional"))
    )
    (net (code "81") (name "GPIO26") (class "Default")
      (node (ref "J2") (pin "87") (pinfunction "GPIO26_87") (pintype "bidirectional"))
    )
    (net (code "82") (name "GPIO27") (class "Default")
      (node (ref "J2") (pin "89") (pinfunction "GPIO27_89") (pintype "bidirectional"))
    )
    (net (code "83") (name "HDMI_LS_OE") (class "Default")
      (node (ref "R13") (pin "1") (pinfunction "1_1") (pintype "passive"))
      (node (ref "R16") (pin "1") (pinfunction "1_1") (pintype "passive"))
      (node (ref "R245") (pin "2") (pinfunction "2_2") (pintype "passive"))
    )
    (net (code "84") (name "I2C0_SCL") (class "Default")
      (node (ref "J2") (pin "5") (pinfunction "GPIO1_5") (pintype "bidirectional"))
      (node (ref "R4") (pin "1") (pinfunction "1_1") (pintype "passive"))
    )
    (net (code "85") (name "I2C0_SDA") (class "Default")
      (node (ref "J2") (pin "3") (pinfunction "GPIO0_3") (pintype "bidirectional"))
      (node (ref "R5") (pin "1") (pinfunction "1_1") (pintype "passive"))
    )
    (net (code "86") (name "I2C1_SCL") (class "Default")
      (node (ref "J2") (pin "11") (pinfunction "GPIO3_11") (pintype "bidirectional"))
      (node (ref "R1") (pin "1") (pinfunction "1_1") (pintype "passive"))
    )
    (net (code "87") (name "I2C1_SDA") (class "Default")
      (node (ref "J2") (pin "9") (pinfunction "GPIO2_9") (pintype "bidirectional"))
      (node (ref "R3") (pin "1") (pinfunction "1_1") (pintype "passive"))
    )
    (net (code "88") (name "Net-(BAT1-+)") (class "Default")
      (node (ref "BAT1") (pin "1") (pinfunction "+_1") (pintype "passive"))
      (node (ref "U23") (pin "3") (pinfunction "VBAT_3") (pintype "power_in"))
    )
    (net (code "89") (name "Net-(J1-+5V)") (class "Default")
      (node (ref "J1") (pin "18") (pinfunction "+5V_18") (pintype "power_in"))
      (node (ref "L1") (pin "2") (pinfunction "2_2") (pintype "passive"))
    )
    (net (code "90") (name "Net-(J1-GND_21)") (class "Default")
      (node (ref "C8") (pin "2") (pinfunction "2_2") (pintype "passive"))
      (node (ref "J1") (pin "21") (pinfunction "GND_21_21") (pintype "power_in"))
      (node (ref "J1") (pin "22") (pinfunction "GND_22_22") (pintype "power_in"))
      (node (ref "J1") (pin "23") (pinfunction "GND_23_23") (pintype "power_in"))
      (node (ref "J1") (pin "24") (pinfunction "GND_24_24") (pintype "power_in"))
    )
    (net (code "91") (name "Net-(J2-DSI0_CN)") (class "Default")
      (node (ref "J2") (pin "105") (pinfunction "DSI0_CN_105") (pintype "output"))
      (node (ref "TP5") (pin "1") (pinfunction "TP_1") (pintype "passive"))
    )
    (net (code "92") (name "Net-(J2-DSI0_CP)") (class "Default")
      (node (ref "J2") (pin "107") (pinfunction "DSI0_CP_107") (pintype "output"))
      (node (ref "TP6") (pin "1") (pinfunction "TP_1") (pintype "passive"))
    )
    (net (code "93") (name "Net-(J2-DSI0_DN0)") (class "Default")
      (node (ref "J2") (pin "99") (pinfunction "DSI0_DN0_99") (pintype "output"))
      (node (ref "TP3") (pin "1") (pinfunction "TP_1") (pintype "passive"))
    )
    (net (code "94") (name "Net-(J2-DSI0_DN1)") (class "Default")
      (node (ref "J2") (pin "93") (pinfunction "DSI0_DN1_93") (pintype "output"))
      (node (ref "TP1") (pin "1") (pinfunction "TP_1") (pintype "passive"))
    )
    (net (code "95") (name "Net-(J2-DSI0_DP0)") (class "Default")
      (node (ref "J2") (pin "101") (pinfunction "DSI0_DP0_101") (pintype "output"))
      (node (ref "TP4") (pin "1") (pinfunction "TP_1") (pintype "passive"))
    )
    (net (code "96") (name "Net-(J2-DSI0_DP1)") (class "Default")
      (node (ref "J2") (pin "95") (pinfunction "DSI0_DP1_95") (pintype "output"))
      (node (ref "TP2") (pin "1") (pinfunction "TP_1") (pintype "passive"))
    )
    (net (code "97") (name "Net-(J2-GPIO28)") (class "Default")
      (node (ref "J2") (pin "28") (pinfunction "GPIO28_28") (pintype "bidirectional"))
      (node (ref "R8") (pin "1") (pinfunction "1_1") (pintype "passive"))
    )
    (net (code "98") (name "Net-(J2-GPIO29)") (class "Default")
      (node (ref "J2") (pin "30") (pinfunction "GPIO29_30") (pintype "bidirectional"))
      (node (ref "R9") (pin "1") (pinfunction "1_1") (pintype "passive"))
    )
    (net (code "99") (name "Net-(J2-GPIO30)") (class "Default")
      (node (ref "J2") (pin "34") (pinfunction "GPIO30_34") (pintype "bidirectional"))
      (node (ref "R11") (pin "1") (pinfunction "1_1") (pintype "passive"))
    )
    (net (code "100") (name "Net-(J2-GPIO31)") (class "Default")
      (node (ref "J2") (pin "36") (pinfunction "GPIO31_36") (pintype "bidirectional"))
      (node (ref "R12") (pin "1") (pinfunction "1_1") (pintype "passive"))
    )
    (net (code "101") (name "Net-(J2-GPIO32)") (class "Default")
      (node (ref "J2") (pin "46") (pinfunction "GPIO32_46") (pintype "bidirectional"))
      (node (ref "R14") (pin "1") (pinfunction "1_1") (pintype "passive"))
    )
    (net (code "102") (name "Net-(J2-GPIO33)") (class "Default")
      (node (ref "J2") (pin "48") (pinfunction "GPIO33_48") (pintype "bidirectional"))
      (node (ref "R15") (pin "1") (pinfunction "1_1") (pintype "passive"))
    )
    (net (code "103") (name "Net-(J2-GPIO40)") (class "Default")
      (node (ref "J2") (pin "70") (pinfunction "GPIO40_70") (pintype "bidirectional"))
      (node (ref "R293") (pin "1") (pinfunction "1_1") (pintype "passive"))
    )
    (net (code "104") (name "Net-(J2-GPIO42)") (class "Default")
      (node (ref "J2") (pin "76") (pinfunction "GPIO42_76") (pintype "bidirectional"))
      (node (ref "R17") (pin "1") (pinfunction "1_1") (pintype "passive"))
    )
    (net (code "105") (name "Net-(J2-GPIO43)") (class "Default")
      (node (ref "J2") (pin "78") (pinfunction "GPIO43_78") (pintype "bidirectional"))
      (node (ref "R19") (pin "1") (pinfunction "1_1") (pintype "passive"))
    )
    (net (code "106") (name "Net-(J2-TVDAC)") (class "Default")
      (node (ref "J2") (pin "166") (pinfunction "TVDAC_166") (pintype "output"))
      (node (ref "R28") (pin "1") (pinfunction "1_1") (pintype "passive"))
    )
    (net (code "107") (name "Net-(J2-USB_OTGID)") (class "Default")
      (node (ref "J2") (pin "168") (pinfunction "USB_OTGID_168") (pintype "input"))
      (node (ref "R29") (pin "1") (pinfunction "1_1") (pintype "passive"))
    )
    (net (code "108") (name "Net-(J2-~{HDMI_HPD_1V8})") (class "Default")
      (node (ref "J2") (pin "88") (pinfunction "~{HDMI_HPD_1V8}_88") (pintype "input"))
      (node (ref "Q1") (pin "3") (pinfunction "D_3") (pintype "passive"))
      (node (ref "R21") (pin "1") (pinfunction "1_1") (pintype "passive"))
    )
    (net (code "109") (name "Net-(LD17-C)") (class "Default")
      (node (ref "LD17") (pin "1") (pinfunction "C_1") (pintype "passive"))
      (node (ref "R31") (pin "2") (pinfunction "2_2") (pintype "passive"))
    )
    (net (code "110") (name "Net-(Q2-G)") (class "Default")
      (node (ref "Q2") (pin "1") (pinfunction "G_1") (pintype "passive"))
      (node (ref "R237") (pin "1") (pinfunction "1_1") (pintype "passive"))
      (node (ref "R32") (pin "2") (pinfunction "2_2") (pintype "passive"))
    )
    (net (code "111") (name "Net-(Q2-S)") (class "Default")
      (node (ref "Q2") (pin "2") (pinfunction "S_2") (pintype "passive"))
      (node (ref "Q3") (pin "3") (pinfunction "D_3") (pintype "passive"))
      (node (ref "R31") (pin "1") (pinfunction "1_1") (pintype "passive"))
    )
    (net (code "112") (name "Net-(R1-Pad2)") (class "Default")
      (node (ref "R1") (pin "2") (pinfunction "2_2") (pintype "passive"))
      (node (ref "R183") (pin "2") (pinfunction "2_2") (pintype "passive"))
      (node (ref "R184") (pin "2") (pinfunction "2_2") (pintype "passive"))
      (node (ref "R3") (pin "2") (pinfunction "2_2") (pintype "passive"))
    )
    (net (code "113") (name "Net-(U1-5V_OUT)") (class "Default")
      (node (ref "C10") (pin "1") (pinfunction "1_1") (pintype "passive"))
      (node (ref "L1") (pin "1") (pinfunction "1_1") (pintype "passive"))
      (node (ref "U1") (pin "12") (pinfunction "5V_OUT_12") (pintype "power_in"))
    )
    (net (code "114") (name "Net-(U1-CEC_A)") (class "Default")
      (node (ref "R6") (pin "2") (pinfunction "2_2") (pintype "passive"))
      (node (ref "U1") (pin "24") (pinfunction "CEC_A_24") (pintype "bidirectional"))
    )
    (net (code "115") (name "Net-(U1-CT_HPD)") (class "Default")
      (node (ref "R16") (pin "2") (pinfunction "2_2") (pintype "passive"))
      (node (ref "U1") (pin "11") (pinfunction "CT_HPD_11") (pintype "input"))
    )
    (net (code "116") (name "Net-(U1-LS_OE)") (class "Default")
      (node (ref "R13") (pin "2") (pinfunction "2_2") (pintype "passive"))
      (node (ref "U1") (pin "4") (pinfunction "LS_OE_4") (pintype "input"))
    )
    (net (code "117") (name "Net-(U1-VCC5V)") (class "Default")
      (node (ref "C9") (pin "1") (pinfunction "1_1") (pintype "passive"))
      (node (ref "R243") (pin "2") (pinfunction "2_2") (pintype "passive"))
      (node (ref "R244") (pin "2") (pinfunction "2_2") (pintype "passive"))
      (node (ref "U1") (pin "10") (pinfunction "VCC5V_10") (pintype "power_in"))
    )
    (net (code "118") (name "Net-(U1-VCCA)") (class "Default")
      (node (ref "C3") (pin "1") (pinfunction "1_1") (pintype "passive"))
      (node (ref "R2") (pin "1") (pinfunction "1_1") (pintype "passive"))
      (node (ref "U1") (pin "23") (pinfunction "VCCA_23") (pintype "power_in"))
    )
    (net (code "119") (name "Net-(U23-X1)") (class "Default")
      (node (ref "U23") (pin "1") (pinfunction "X1_1") (pintype "passive"))
      (node (ref "Y4") (pin "2") (pinfunction "2_2") (pintype "passive"))
    )
    (net (code "120") (name "Net-(U23-X2)") (class "Default")
      (node (ref "U23") (pin "2") (pinfunction "X2_2") (pintype "passive"))
      (node (ref "Y4") (pin "1") (pinfunction "1_1") (pintype "passive"))
    )
    (net (code "121") (name "SEL_SWD") (class "Default")
      (node (ref "J2") (pin "72") (pinfunction "GPIO41_72") (pintype "bidirectional"))
    )
    (net (code "122") (name "SW_I2C_SCL_ON") (class "Default")
      (node (ref "U23") (pin "6") (pinfunction "SCL_6") (pintype "input"))
    )
    (net (code "123") (name "SW_I2C_SCL_ON_OFF") (class "Default")
      (node (ref "R17") (pin "2") (pinfunction "2_2") (pintype "passive"))
    )
    (net (code "124") (name "SW_I2C_SDA_ON") (class "Default")
      (node (ref "U23") (pin "5") (pinfunction "SDA_5") (pintype "bidirectional"))
    )
    (net (code "125") (name "SW_I2C_SDA_ON_OFF") (class "Default")
      (node (ref "R19") (pin "2") (pinfunction "2_2") (pintype "passive"))
    )
    (net (code "126") (name "USB_DM") (class "Default")
      (node (ref "J2") (pin "167") (pinfunction "USB_DM_167") (pintype "bidirectional"))
    )
    (net (code "127") (name "USB_DP") (class "Default")
      (node (ref "J2") (pin "165") (pinfunction "USB_DP_165") (pintype "bidirectional"))
    )
    (net (code "128") (name "WIFI_BLE_PDN") (class "Default")
      (node (ref "R293") (pin "2") (pinfunction "2_2") (pintype "passive"))
    )
    (net (code "129") (name "WIFI_SDIO_CLK") (class "Default")
      (node (ref "J2") (pin "52") (pinfunction "GPIO34_52") (pintype "bidirectional"))
    )
    (net (code "130") (name "WIFI_SDIO_CMD") (class "Default")
      (node (ref "J2") (pin "54") (pinfunction "GPIO35_54") (pintype "bidirectional"))
    )
    (net (code "131") (name "WIFI_SDIO_D0") (class "Default")
      (node (ref "J2") (pin "58") (pinfunction "GPIO36_58") (pintype "bidirectional"))
    )
    (net (code "132") (name "WIFI_SDIO_D1") (class "Default")
      (node (ref "J2") (pin "60") (pinfunction "GPIO37_60") (pintype "bidirectional"))
    )
    (net (code "133") (name "WIFI_SDIO_D2") (class "Default")
      (node (ref "J2") (pin "64") (pinfunction "GPIO38_64") (pintype "bidirectional"))
    )
    (net (code "134") (name "WIFI_SDIO_D3") (class "Default")
      (node (ref "J2") (pin "66") (pinfunction "GPIO39_66") (pintype "bidirectional"))
    )
    (net (code "135") (name "eMMC_CLK") (class "Default")
      (node (ref "J2") (pin "10") (pinfunction "SDX_CLK_10") (pintype "output"))
    )
    (net (code "136") (name "eMMC_CMD") (class "Default")
      (node (ref "J2") (pin "12") (pinfunction "SDX_CMD_12") (pintype "bidirectional"))
    )
    (net (code "137") (name "eMMC_D0") (class "Default")
      (node (ref "J2") (pin "16") (pinfunction "SDX_D0_16") (pintype "bidirectional"))
    )
    (net (code "138") (name "eMMC_D1") (class "Default")
      (node (ref "J2") (pin "18") (pinfunction "SDX_D1_18") (pintype "bidirectional"))
    )
    (net (code "139") (name "eMMC_D2") (class "Default")
      (node (ref "J2") (pin "22") (pinfunction "SDX_D2_22") (pintype "bidirectional"))
    )
    (net (code "140") (name "eMMC_D3") (class "Default")
      (node (ref "J2") (pin "24") (pinfunction "SDX_D3_24") (pintype "bidirectional"))
    )
    (net (code "141") (name "unconnected-(J1-RES-Pad14)") (class "Default")
      (node (ref "J1") (pin "14") (pinfunction "RES_14") (pintype "passive"))
    )
    (net (code "142") (name "unconnected-(J2-CAM1_DN2-Pad143)") (class "Default")
      (node (ref "J2") (pin "143") (pinfunction "CAM1_DN2_143") (pintype "input+no_connect"))
    )
    (net (code "143") (name "unconnected-(J2-CAM1_DN3-Pad137)") (class "Default")
      (node (ref "J2") (pin "137") (pinfunction "CAM1_DN3_137") (pintype "input+no_connect"))
    )
    (net (code "144") (name "unconnected-(J2-CAM1_DP2-Pad141)") (class "Default")
      (node (ref "J2") (pin "141") (pinfunction "CAM1_DP2_141") (pintype "input+no_connect"))
    )
    (net (code "145") (name "unconnected-(J2-CAM1_DP3-Pad135)") (class "Default")
      (node (ref "J2") (pin "135") (pinfunction "CAM1_DP3_135") (pintype "input+no_connect"))
    )
    (net (code "146") (name "unconnected-(J2-DSI1_DN2-Pad114)") (class "Default")
      (node (ref "J2") (pin "114") (pinfunction "DSI1_DN2_114") (pintype "output"))
    )
    (net (code "147") (name "unconnected-(J2-DSI1_DN3-Pad108)") (class "Default")
      (node (ref "J2") (pin "108") (pinfunction "DSI1_DN3_108") (pintype "output"))
    )
    (net (code "148") (name "unconnected-(J2-DSI1_DP2-Pad112)") (class "Default")
      (node (ref "J2") (pin "112") (pinfunction "DSI1_DP2_112") (pintype "output"))
    )
    (net (code "149") (name "unconnected-(J2-DSI1_DP3-Pad106)") (class "Default")
      (node (ref "J2") (pin "106") (pinfunction "DSI1_DP3_106") (pintype "output"))
    )
    (net (code "150") (name "unconnected-(J2-NC124-Pad124)") (class "Default")
      (node (ref "J2") (pin "124") (pinfunction "NC124_124") (pintype "passive+no_connect"))
    )
    (net (code "151") (name "unconnected-(J2-NC126-Pad126)") (class "Default")
      (node (ref "J2") (pin "126") (pinfunction "NC126_126") (pintype "passive+no_connect"))
    )
    (net (code "152") (name "unconnected-(J2-NC128-Pad128)") (class "Default")
      (node (ref "J2") (pin "128") (pinfunction "NC128_128") (pintype "passive+no_connect"))
    )
    (net (code "153") (name "unconnected-(J2-NC130-Pad130)") (class "Default")
      (node (ref "J2") (pin "130") (pinfunction "NC130_130") (pintype "passive+no_connect"))
    )
    (net (code "154") (name "unconnected-(J2-NC132-Pad132)") (class "Default")
      (node (ref "J2") (pin "132") (pinfunction "NC132_132") (pintype "passive+no_connect"))
    )
    (net (code "155") (name "unconnected-(J2-NC154-Pad154)") (class "Default")
      (node (ref "J2") (pin "154") (pinfunction "NC154_154") (pintype "passive+no_connect"))
    )
    (net (code "156") (name "unconnected-(J2-NC156-Pad156)") (class "Default")
      (node (ref "J2") (pin "156") (pinfunction "NC156_156") (pintype "passive+no_connect"))
    )
    (net (code "157") (name "unconnected-(J2-NC158-Pad158)") (class "Default")
      (node (ref "J2") (pin "158") (pinfunction "NC158_158") (pintype "passive+no_connect"))
    )
    (net (code "158") (name "unconnected-(J2-NC160-Pad160)") (class "Default")
      (node (ref "J2") (pin "160") (pinfunction "NC160_160") (pintype "passive+no_connect"))
    )
    (net (code "159") (name "unconnected-(J2-NC162-Pad162)") (class "Default")
      (node (ref "J2") (pin "162") (pinfunction "NC162_162") (pintype "passive+no_connect"))
    )
    (net (code "160") (name "unconnected-(J2-NC179-Pad179)") (class "Default")
      (node (ref "J2") (pin "179") (pinfunction "NC179_179") (pintype "passive+no_connect"))
    )
    (net (code "161") (name "unconnected-(J2-RUN-Pad177)") (class "Default")
      (node (ref "J2") (pin "177") (pinfunction "RUN_177") (pintype "input+no_connect"))
    )
    (net (code "162") (name "unconnected-(U23-SWQ{slash}OUT-Pad7)") (class "Default")
      (node (ref "U23") (pin "7") (pinfunction "SWQ/OUT_7") (pintype "passive"))
    )
  )
)
